# sb-sonata-psu.net
KiCad netlist of a schematic drawn in Altium Designer
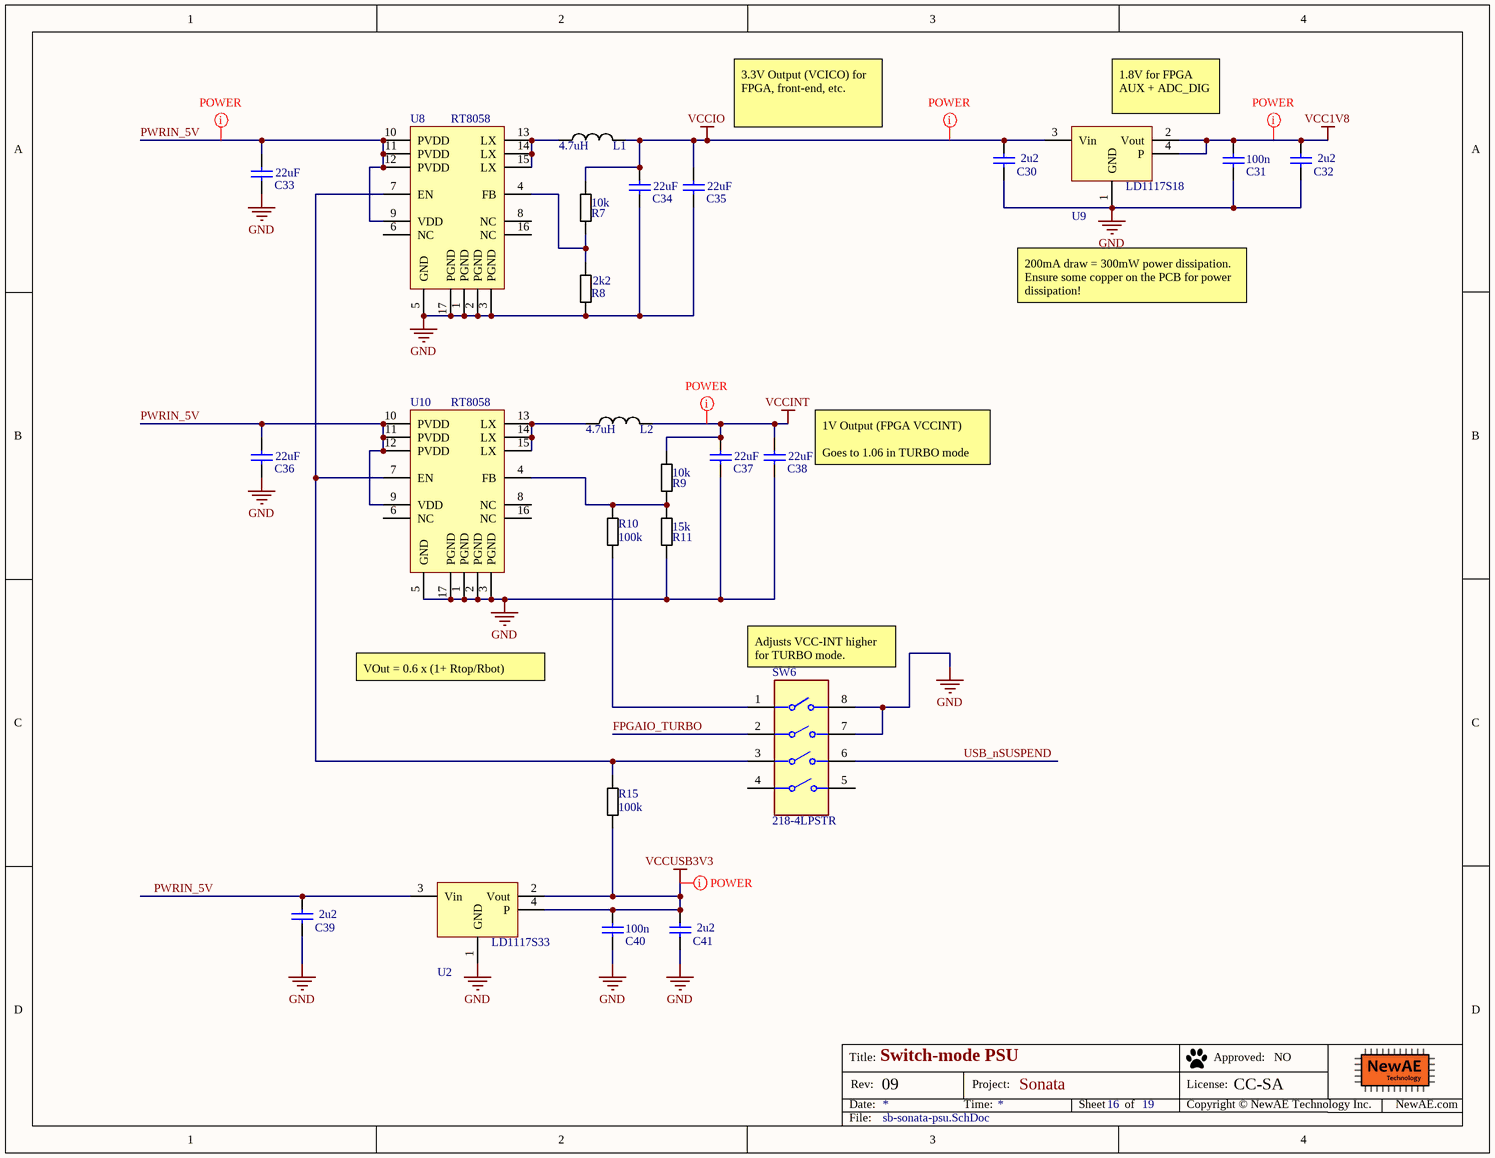
[diagram p0: sb-sonata-psu.SchDoc]

(export (version "E")
  (design (tool "Eeschema 10.0.6"))
  (components
    (comp (ref "C30")
      (value "2u2")
      (footprint "CAPC0603_M")
      (description "2u2, 0603")
      (fields (field (name "PART NUMBER") "CCHIP-2u2-0603"))
      (libsource (lib "NewAE_AltiumLib") (part "CAP"))
    )
    (comp (ref "C31")
      (value "100n")
      (footprint "CAPC0402_M")
      (description "100n, 0402")
      (fields (field (name "PART NUMBER") "CCHIP-100n-0402"))
      (libsource (lib "NewAE_AltiumLib") (part "CAP"))
    )
    (comp (ref "C32")
      (value "2u2")
      (footprint "CAPC0603_M")
      (description "2u2, 0603")
      (fields (field (name "PART NUMBER") "CCHIP-2u2-0603"))
      (libsource (lib "NewAE_AltiumLib") (part "CAP"))
    )
    (comp (ref "C33")
      (value "22uF")
      (footprint "CAPC0805_M")
      (description "22u, 16V, 0805, Ceramic")
      (fields (field (name "PART NUMBER") "CCHIP-22u-0805-16V") (field (name "TOLERANCE") "20%"))
      (libsource (lib "NewAE_AltiumLib") (part "CAP"))
    )
    (comp (ref "C34")
      (value "22uF")
      (footprint "CAPC0805_M")
      (description "22u, 16V, 0805, Ceramic")
      (fields (field (name "PART NUMBER") "CCHIP-22u-0805-16V") (field (name "TOLERANCE") "20%"))
      (libsource (lib "NewAE_AltiumLib") (part "CAP"))
    )
    (comp (ref "C35")
      (value "22uF")
      (footprint "CAPC0805_M")
      (description "22u, 16V, 0805, Ceramic")
      (fields (field (name "PART NUMBER") "CCHIP-22u-0805-16V") (field (name "TOLERANCE") "20%"))
      (libsource (lib "NewAE_AltiumLib") (part "CAP"))
    )
    (comp (ref "C36")
      (value "22uF")
      (footprint "CAPC0805_M")
      (description "22u, 16V, 0805, Ceramic")
      (fields (field (name "PART NUMBER") "CCHIP-22u-0805-16V") (field (name "TOLERANCE") "20%"))
      (libsource (lib "NewAE_AltiumLib") (part "CAP"))
    )
    (comp (ref "C37")
      (value "22uF")
      (footprint "CAPC0805_M")
      (description "22u, 16V, 0805, Ceramic")
      (fields (field (name "PART NUMBER") "CCHIP-22u-0805-16V") (field (name "TOLERANCE") "20%"))
      (libsource (lib "NewAE_AltiumLib") (part "CAP"))
    )
    (comp (ref "C38")
      (value "22uF")
      (footprint "CAPC0805_M")
      (description "22u, 16V, 0805, Ceramic")
      (fields (field (name "PART NUMBER") "CCHIP-22u-0805-16V") (field (name "TOLERANCE") "20%"))
      (libsource (lib "NewAE_AltiumLib") (part "CAP"))
    )
    (comp (ref "C39")
      (value "2u2")
      (footprint "CAPC0603_M")
      (description "2u2, 0603")
      (fields (field (name "PART NUMBER") "CCHIP-2u2-0603"))
      (libsource (lib "NewAE_AltiumLib") (part "CAP"))
    )
    (comp (ref "C40")
      (value "100n")
      (footprint "CAPC0402_M")
      (description "100n, 0402")
      (fields (field (name "PART NUMBER") "CCHIP-100n-0402"))
      (libsource (lib "NewAE_AltiumLib") (part "CAP"))
    )
    (comp (ref "C41")
      (value "2u2")
      (footprint "CAPC0603_M")
      (description "2u2, 0603")
      (fields (field (name "PART NUMBER") "CCHIP-2u2-0603"))
      (libsource (lib "NewAE_AltiumLib") (part "CAP"))
    )
    (comp (ref "L1")
      (value "4.7uH")
      (footprint "NR6028")
      (description "fixed ind, ferrite, shielded")
      (fields (field (name "PART NUMBER") "NR6028T4R7M"))
      (libsource (lib "NewAE_AltiumLib") (part "IND"))
    )
    (comp (ref "L2")
      (value "4.7uH")
      (footprint "NR6028")
      (description "fixed ind, ferrite, shielded")
      (fields (field (name "PART NUMBER") "NR6028T4R7M"))
      (libsource (lib "NewAE_AltiumLib") (part "IND"))
    )
    (comp (ref "R7")
      (value "10k")
      (footprint "RESC1005X40N")
      (description "10k res, 0402, 1%, 1/16W")
      (fields (field (name "PART NUMBER") "RCHIP-10K-0402") (field (name "TOLERANCE") "1%"))
      (libsource (lib "NewAE_AltiumLib") (part "RES-EU"))
    )
    (comp (ref "R8")
      (value "2k2")
      (footprint "RESC1005X40N")
      (description "2k2 res, 0402, 1%, 1/16W")
      (fields (field (name "PART NUMBER") "RCHIP-2K2-0402") (field (name "TOLERANCE") "1%"))
      (libsource (lib "NewAE_AltiumLib") (part "RES-EU"))
    )
    (comp (ref "R9")
      (value "10k")
      (footprint "RESC1005X40N")
      (description "10k res, 0402, 1%, 1/16W")
      (fields (field (name "PART NUMBER") "RCHIP-10K-0402") (field (name "TOLERANCE") "1%"))
      (libsource (lib "NewAE_AltiumLib") (part "RES-EU"))
    )
    (comp (ref "R10")
      (value "100k")
      (footprint "RESC1005X40N")
      (description "100k res, 0402, 1%, 1/16W")
      (fields (field (name "PART NUMBER") "RCHIP-100K-0402") (field (name "TOLERANCE") "1%"))
      (libsource (lib "NewAE_AltiumLib") (part "RES-EU"))
    )
    (comp (ref "R11")
      (value "15k")
      (footprint "RESC1005X40N")
      (description "15k res, 0402, 1%, 1/16W")
      (fields (field (name "PART NUMBER") "RCHIP-15K-0402") (field (name "TOLERANCE") "1%"))
      (libsource (lib "NewAE_AltiumLib") (part "RES-EU"))
    )
    (comp (ref "R15")
      (value "100k")
      (footprint "RESC1608X55N")
      (description "100k res, 0603, 1%, 1/10W")
      (fields (field (name "PART NUMBER") "RCHIP-100K-0603") (field (name "TOLERANCE") "1%"))
      (libsource (lib "") (part "RES-EU_1"))
    )
    (comp (ref "SW6")
      (value "218-4LPSTR")
      (footprint "FP-218-4LPSTR-MFG")
      (description "SWITCH SLIDE DIP SPST 25MA 24V")
      (libsource (lib "Altium Content Vault") (part "a78650ae27aee94b64e9c93150c7d5d"))
    )
    (comp (ref "U2")
      (value "LD1117S33")
      (footprint "SOT-223")
      (description "IC REG LIN POS 3.3V 800MA SOT223")
      (libsource (lib "NewAE_AltiumLib") (part "LD1117S33"))
    )
    (comp (ref "U8")
      (value "RT8058")
      (footprint "QFN16_50P300X300X100_HS-17M")
      (description "Switching supply controller, 2A")
      (libsource (lib "NewAE_AltiumLib") (part "RT8058"))
    )
    (comp (ref "U9")
      (value "LD1117S18")
      (footprint "SOT-223")
      (description "IC REG LIN POS 1.8V 800MA SOT223")
      (libsource (lib "NewAE_AltiumLib") (part "LD1117S33"))
    )
    (comp (ref "U10")
      (value "RT8058")
      (footprint "QFN16_50P300X300X100_HS-17M")
      (description "Switching supply controller, 2A")
      (libsource (lib "NewAE_AltiumLib") (part "RT8058"))
    )
  )
  (nets
    (net (code "1") (name "/FPGAIO_TURBO") (class "Default")
      (node (ref "SW6") (pin "2") (pinfunction "2_2") (pintype "passive"))
    )
    (net (code "2") (name "/PWRIN_5V") (class "Default")
      (node (ref "C33") (pin "1") (pinfunction "1_1") (pintype "passive"))
      (node (ref "C36") (pin "1") (pinfunction "1_1") (pintype "passive"))
      (node (ref "C39") (pin "1") (pinfunction "1_1") (pintype "passive"))
      (node (ref "U10") (pin "10") (pinfunction "PVDD_10") (pintype "passive"))
      (node (ref "U10") (pin "11") (pinfunction "PVDD_11") (pintype "passive"))
      (node (ref "U10") (pin "12") (pinfunction "PVDD_12") (pintype "passive"))
      (node (ref "U10") (pin "9") (pinfunction "VDD_9") (pintype "passive"))
      (node (ref "U2") (pin "3") (pinfunction "Vin_3") (pintype "passive"))
      (node (ref "U8") (pin "10") (pinfunction "PVDD_10") (pintype "passive"))
      (node (ref "U8") (pin "11") (pinfunction "PVDD_11") (pintype "passive"))
      (node (ref "U8") (pin "12") (pinfunction "PVDD_12") (pintype "passive"))
      (node (ref "U8") (pin "9") (pinfunction "VDD_9") (pintype "passive"))
    )
    (net (code "3") (name "/USB_nSUSPEND") (class "Default")
      (node (ref "SW6") (pin "6") (pinfunction "6_6") (pintype "passive"))
    )
    (net (code "4") (name "GND") (class "Default")
      (node (ref "C30") (pin "2") (pinfunction "2_2") (pintype "passive"))
      (node (ref "C31") (pin "2") (pinfunction "2_2") (pintype "passive"))
      (node (ref "C32") (pin "2") (pinfunction "2_2") (pintype "passive"))
      (node (ref "C33") (pin "2") (pinfunction "2_2") (pintype "passive"))
      (node (ref "C34") (pin "2") (pinfunction "2_2") (pintype "passive"))
      (node (ref "C35") (pin "2") (pinfunction "2_2") (pintype "passive"))
      (node (ref "C36") (pin "2") (pinfunction "2_2") (pintype "passive"))
      (node (ref "C37") (pin "2") (pinfunction "2_2") (pintype "passive"))
      (node (ref "C38") (pin "2") (pinfunction "2_2") (pintype "passive"))
      (node (ref "C39") (pin "2") (pinfunction "2_2") (pintype "passive"))
      (node (ref "C40") (pin "2") (pinfunction "2_2") (pintype "passive"))
      (node (ref "C41") (pin "2") (pinfunction "2_2") (pintype "passive"))
      (node (ref "R11") (pin "2") (pinfunction "2_2") (pintype "passive"))
      (node (ref "R8") (pin "2") (pinfunction "2_2") (pintype "passive"))
      (node (ref "SW6") (pin "7") (pinfunction "7_7") (pintype "passive"))
      (node (ref "SW6") (pin "8") (pinfunction "8_8") (pintype "passive"))
      (node (ref "U10") (pin "1") (pinfunction "PGND_1") (pintype "passive"))
      (node (ref "U10") (pin "17") (pinfunction "PGND_17") (pintype "passive"))
      (node (ref "U10") (pin "2") (pinfunction "PGND_2") (pintype "passive"))
      (node (ref "U10") (pin "3") (pinfunction "PGND_3") (pintype "passive"))
      (node (ref "U10") (pin "5") (pinfunction "GND_5") (pintype "passive"))
      (node (ref "U2") (pin "1") (pinfunction "GND_1") (pintype "passive"))
      (node (ref "U8") (pin "1") (pinfunction "PGND_1") (pintype "passive"))
      (node (ref "U8") (pin "17") (pinfunction "PGND_17") (pintype "passive"))
      (node (ref "U8") (pin "2") (pinfunction "PGND_2") (pintype "passive"))
      (node (ref "U8") (pin "3") (pinfunction "PGND_3") (pintype "passive"))
      (node (ref "U8") (pin "5") (pinfunction "GND_5") (pintype "passive"))
      (node (ref "U9") (pin "1") (pinfunction "GND_1") (pintype "passive"))
    )
    (net (code "5") (name "Net-(L1-Pad1)") (class "Default")
      (node (ref "L1") (pin "1") (pinfunction "1_1") (pintype "passive"))
      (node (ref "U8") (pin "13") (pinfunction "LX_13") (pintype "passive"))
      (node (ref "U8") (pin "14") (pinfunction "LX_14") (pintype "passive"))
      (node (ref "U8") (pin "15") (pinfunction "LX_15") (pintype "passive"))
    )
    (net (code "6") (name "Net-(L2-Pad1)") (class "Default")
      (node (ref "L2") (pin "1") (pinfunction "1_1") (pintype "passive"))
      (node (ref "U10") (pin "13") (pinfunction "LX_13") (pintype "passive"))
      (node (ref "U10") (pin "14") (pinfunction "LX_14") (pintype "passive"))
      (node (ref "U10") (pin "15") (pinfunction "LX_15") (pintype "passive"))
    )
    (net (code "7") (name "Net-(R10-Pad2)") (class "Default")
      (node (ref "R10") (pin "2") (pinfunction "2_2") (pintype "passive"))
      (node (ref "SW6") (pin "1") (pinfunction "1_1") (pintype "passive"))
    )
    (net (code "8") (name "Net-(U8-FB)") (class "Default")
      (node (ref "R7") (pin "2") (pinfunction "2_2") (pintype "passive"))
      (node (ref "R8") (pin "1") (pinfunction "1_1") (pintype "passive"))
      (node (ref "U8") (pin "4") (pinfunction "FB_4") (pintype "passive"))
    )
    (net (code "9") (name "Net-(U10-EN)") (class "Default")
      (node (ref "R15") (pin "2") (pinfunction "2_2") (pintype "passive"))
      (node (ref "SW6") (pin "3") (pinfunction "3_3") (pintype "passive"))
      (node (ref "U10") (pin "7") (pinfunction "EN_7") (pintype "passive"))
      (node (ref "U8") (pin "7") (pinfunction "EN_7") (pintype "passive"))
    )
    (net (code "10") (name "Net-(U10-FB)") (class "Default")
      (node (ref "R10") (pin "1") (pinfunction "1_1") (pintype "passive"))
      (node (ref "R11") (pin "1") (pinfunction "1_1") (pintype "passive"))
      (node (ref "R9") (pin "2") (pinfunction "2_2") (pintype "passive"))
      (node (ref "U10") (pin "4") (pinfunction "FB_4") (pintype "passive"))
    )
    (net (code "11") (name "VCC1V8") (class "Default")
      (node (ref "C31") (pin "1") (pinfunction "1_1") (pintype "passive"))
      (node (ref "C32") (pin "1") (pinfunction "1_1") (pintype "passive"))
      (node (ref "U9") (pin "2") (pinfunction "Vout_2") (pintype "passive"))
      (node (ref "U9") (pin "4") (pinfunction "P_4") (pintype "passive"))
    )
    (net (code "12") (name "VCCINT") (class "Default")
      (node (ref "C37") (pin "1") (pinfunction "1_1") (pintype "passive"))
      (node (ref "C38") (pin "1") (pinfunction "1_1") (pintype "passive"))
      (node (ref "L2") (pin "2") (pinfunction "2_2") (pintype "passive"))
      (node (ref "R9") (pin "1") (pinfunction "1_1") (pintype "passive"))
    )
    (net (code "13") (name "VCCIO") (class "Default")
      (node (ref "C30") (pin "1") (pinfunction "1_1") (pintype "passive"))
      (node (ref "C34") (pin "1") (pinfunction "1_1") (pintype "passive"))
      (node (ref "C35") (pin "1") (pinfunction "1_1") (pintype "passive"))
      (node (ref "L1") (pin "2") (pinfunction "2_2") (pintype "passive"))
      (node (ref "R7") (pin "1") (pinfunction "1_1") (pintype "passive"))
      (node (ref "U9") (pin "3") (pinfunction "Vin_3") (pintype "passive"))
    )
    (net (code "14") (name "VCCUSB3V3") (class "Default")
      (node (ref "C40") (pin "1") (pinfunction "1_1") (pintype "passive"))
      (node (ref "C41") (pin "1") (pinfunction "1_1") (pintype "passive"))
      (node (ref "R15") (pin "1") (pinfunction "1_1") (pintype "passive"))
      (node (ref "U2") (pin "2") (pinfunction "Vout_2") (pintype "passive"))
      (node (ref "U2") (pin "4") (pinfunction "P_4") (pintype "passive"))
    )
    (net (code "15") (name "unconnected-(SW6-Pad4)") (class "Default")
      (node (ref "SW6") (pin "4") (pinfunction "4_4") (pintype "passive"))
    )
    (net (code "16") (name "unconnected-(SW6-Pad5)") (class "Default")
      (node (ref "SW6") (pin "5") (pinfunction "5_5") (pintype "passive"))
    )
    (net (code "17") (name "unconnected-(U8-NC-Pad6)") (class "Default")
      (node (ref "U8") (pin "6") (pinfunction "NC_6") (pintype "passive"))
    )
    (net (code "18") (name "unconnected-(U8-NC-Pad8)") (class "Default")
      (node (ref "U8") (pin "8") (pinfunction "NC_8") (pintype "passive"))
    )
    (net (code "19") (name "unconnected-(U8-NC-Pad16)") (class "Default")
      (node (ref "U8") (pin "16") (pinfunction "NC_16") (pintype "passive"))
    )
    (net (code "20") (name "unconnected-(U10-NC-Pad6)") (class "Default")
      (node (ref "U10") (pin "6") (pinfunction "NC_6") (pintype "passive"))
    )
    (net (code "21") (name "unconnected-(U10-NC-Pad8)") (class "Default")
      (node (ref "U10") (pin "8") (pinfunction "NC_8") (pintype "passive"))
    )
    (net (code "22") (name "unconnected-(U10-NC-Pad16)") (class "Default")
      (node (ref "U10") (pin "16") (pinfunction "NC_16") (pintype "passive"))
    )
  )
)
